# E17-04-Energy_Meter.net
KiCad netlist of a schematic drawn in Altium Designer
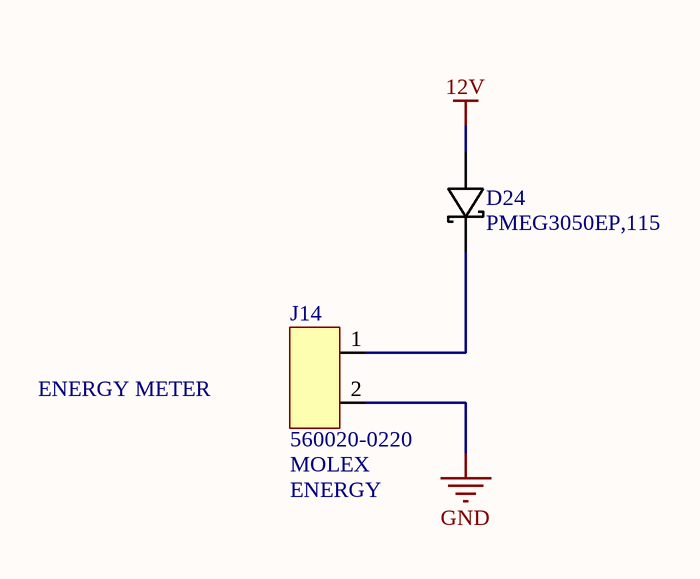
[diagram p0: E17-04-Energy_Meter.SchDoc]

(export (version "E")
  (design (tool "Eeschema 10.0.6"))
  (components
    (comp (ref "D24")
      (value "D_PMEG3050EP,115")
      (footprint "SOD-128")
      (description "DIODE SCHOTTKY 360mV 30V 5A")
      (fields (field (name "MFG") "Nexperia") (field (name "MFG_PN") "PMEG3050EP,115"))
      (libsource (lib "Compiled_PDU") (part "D_PMEG3050EP,115"))
    )
    (comp (ref "J14")
      (value "ENERGY")
      (footprint "MOLEX_DURACLIK_2 NAT VERT")
      (description "MOLEX DURACLIK 2-PIN VERT NAT")
      (fields
        (field (name "VOLTAGE") "125")
        (field (name "MPN") "560020-0220")
        (field (name "MANUFACTURER") "MOLEX")
      )
      (libsource (lib "Molex_DuraClik") (part "560020-0220"))
    )
  )
  (nets
    (net (code "1") (name "12V") (class "Default") (node (ref "D24") (pin "1") (pintype "passive")))
    (net (code "2") (name "GND") (class "Default")
      (node (ref "J14") (pin "2") (pinfunction "2_2") (pintype "passive"))
    )
    (net (code "3") (name "Net-(D24-Pad2)") (class "Default")
      (node (ref "D24") (pin "2") (pintype "passive"))
      (node (ref "J14") (pin "1") (pinfunction "1_1") (pintype "passive"))
    )
  )
)
